# Poloneira.net
KiCad netlist of a schematic drawn in EAGLE
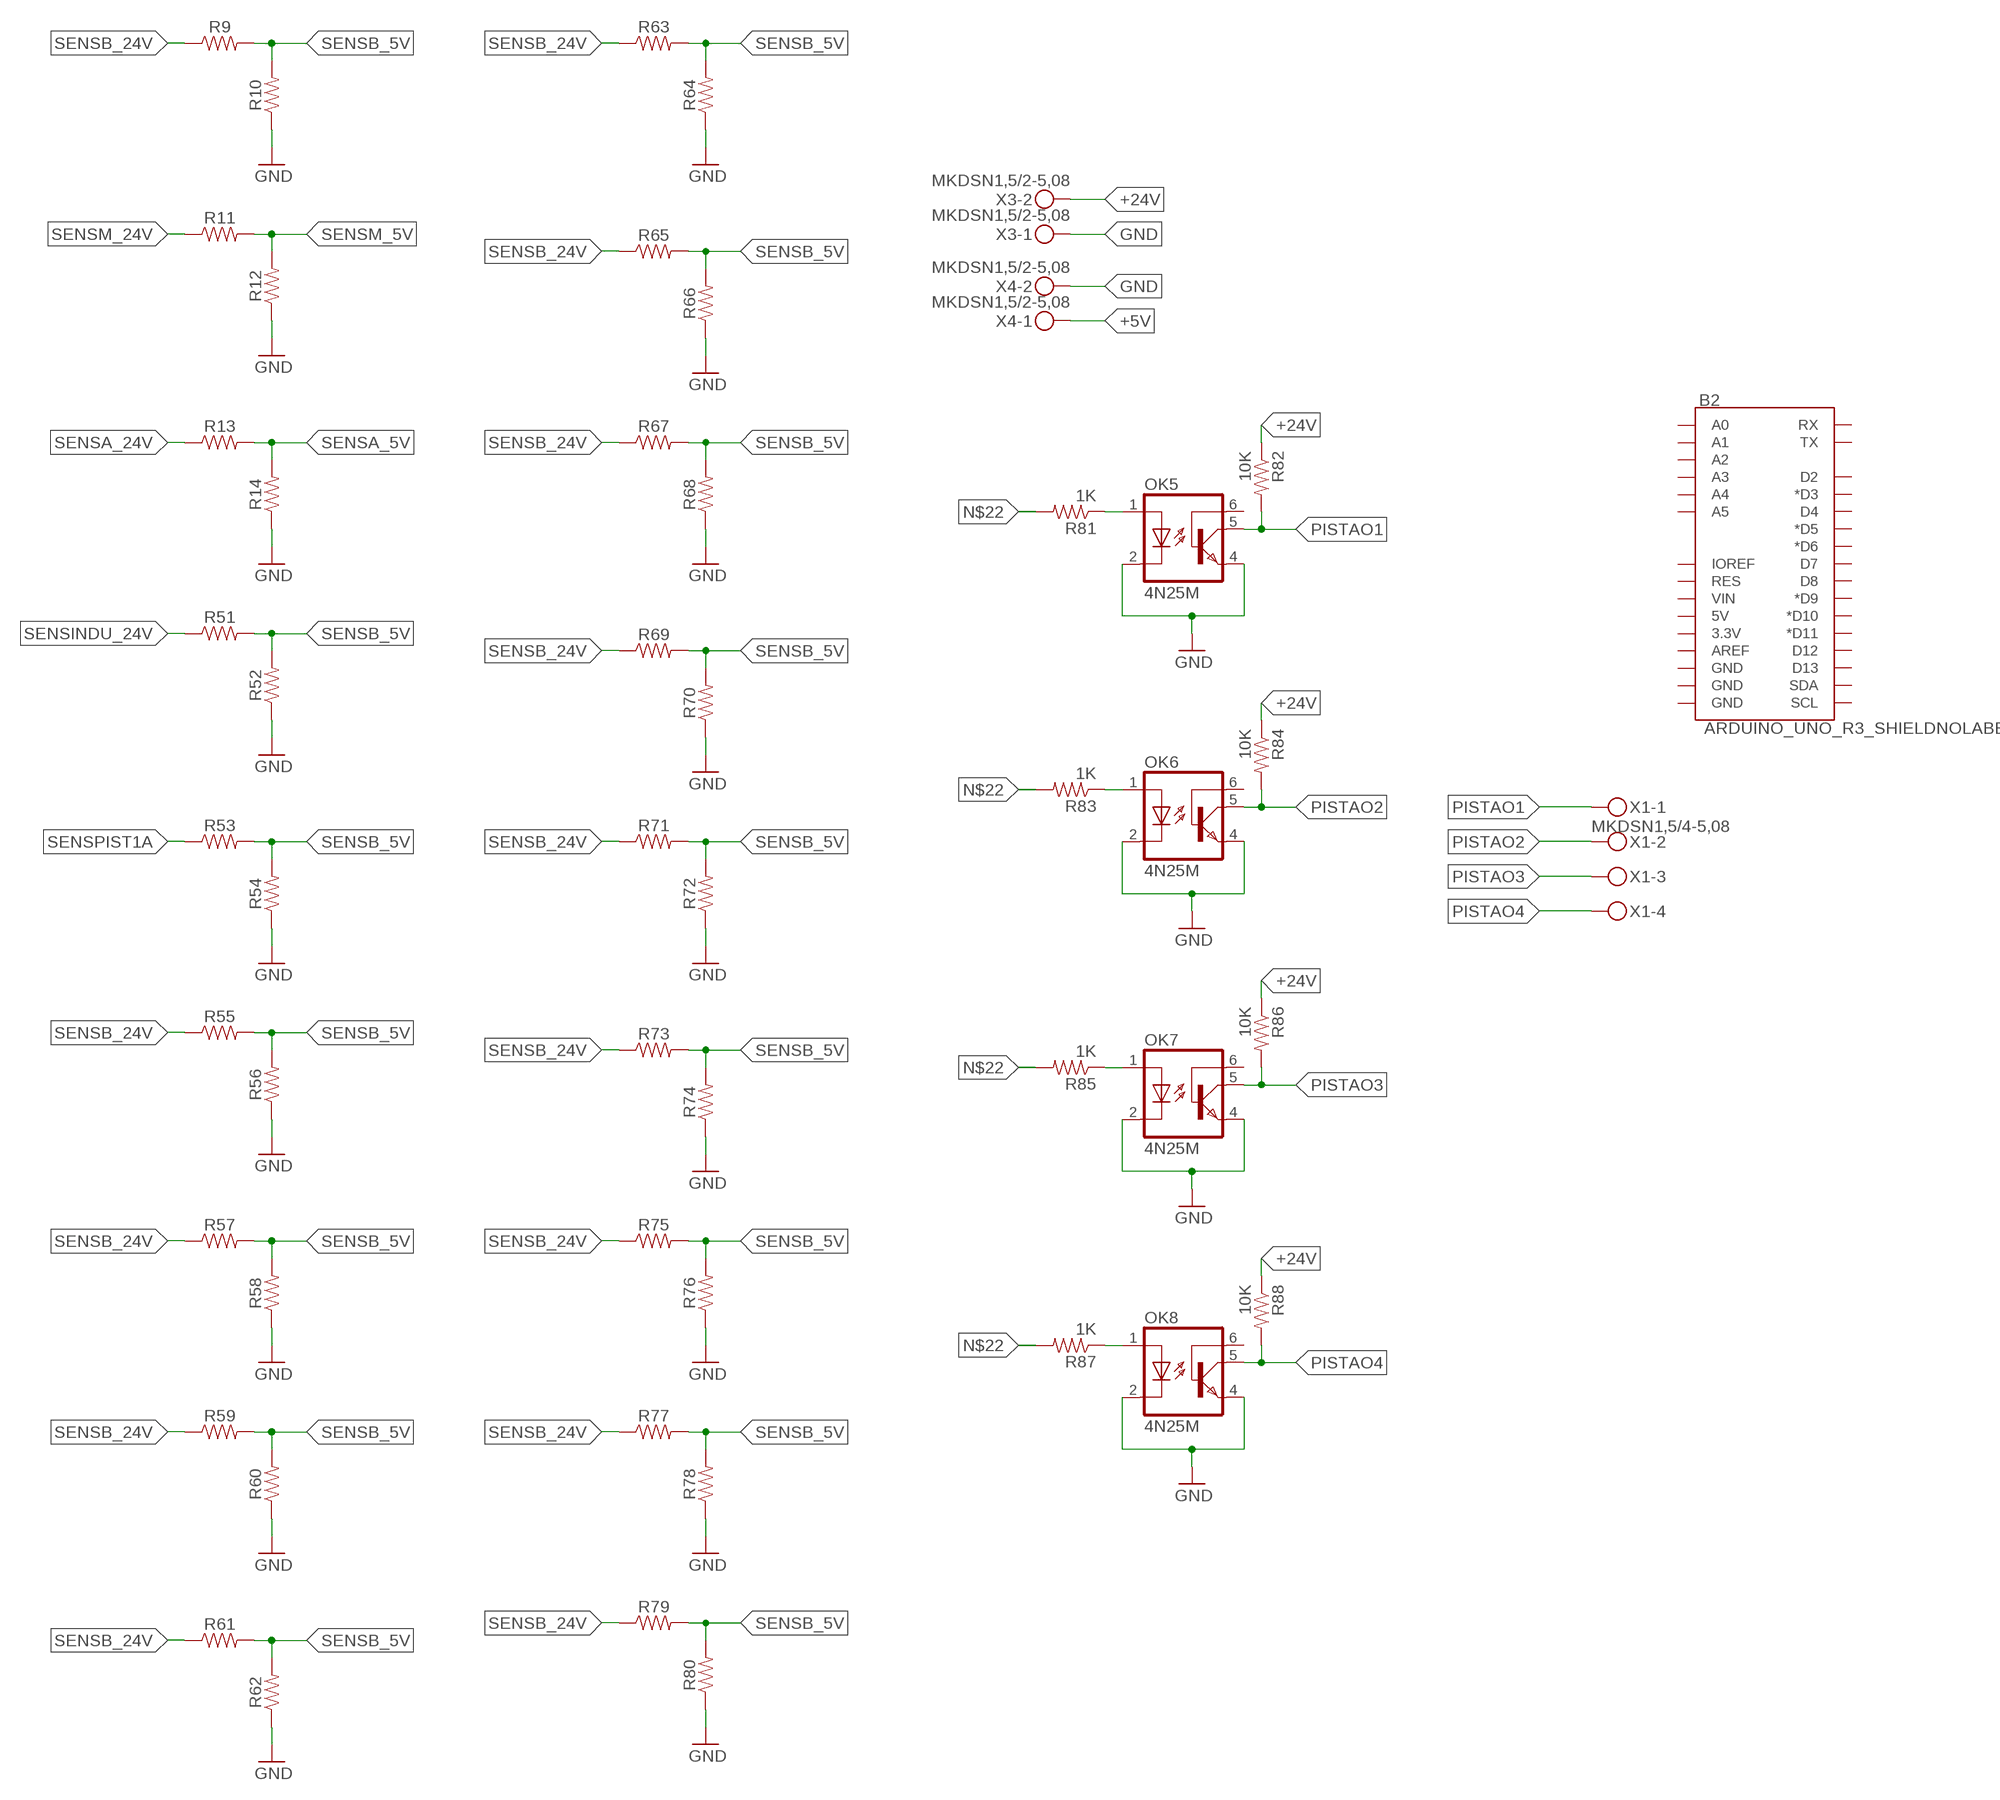
[diagram p0: schematic, sheet 1]

(export (version "E")
  (design (tool "Eeschema 10.0.6"))
  (components
    (comp (ref "B2")
      (value "ARDUINO_UNO_R3_SHIELDNOLABELS")
      (footprint "eagle-import:UNO_R3_SHIELD_NOLABELS")
      (libsource (lib "eagle-import") (part "ARDUINO_UNO_R3_SHIELDNOLABELS"))
    )
    (comp (ref "OK5")
      (value "4N25M")
      (footprint "eagle-import:DIL06")
      (fields (field (name "MPN") "4N25-M"))
      (libsource (lib "eagle-import") (part "4N?M25"))
    )
    (comp (ref "OK6")
      (value "4N25M")
      (footprint "eagle-import:DIL06")
      (fields (field (name "MPN") "4N25-M"))
      (libsource (lib "eagle-import") (part "4N?M25"))
    )
    (comp (ref "OK7")
      (value "4N25M")
      (footprint "eagle-import:DIL06")
      (fields (field (name "MPN") "4N25-M"))
      (libsource (lib "eagle-import") (part "4N?M25"))
    )
    (comp (ref "OK8")
      (value "4N25M")
      (footprint "eagle-import:DIL06")
      (fields (field (name "MPN") "4N25-M"))
      (libsource (lib "eagle-import") (part "4N?M25"))
    )
    (comp (ref "R9")
      (value "RESISTORAXIAL-0.3-KIT")
      (footprint "eagle-import:AXIAL-0.3-KIT")
      (libsource (lib "eagle-import") (part "RESISTORAXIAL-0.3-KIT"))
    )
    (comp (ref "R10")
      (value "RESISTORAXIAL-0.3-KIT")
      (footprint "eagle-import:AXIAL-0.3-KIT")
      (libsource (lib "eagle-import") (part "RESISTORAXIAL-0.3-KIT"))
    )
    (comp (ref "R11")
      (value "RESISTORAXIAL-0.3-KIT")
      (footprint "eagle-import:AXIAL-0.3-KIT")
      (libsource (lib "eagle-import") (part "RESISTORAXIAL-0.3-KIT"))
    )
    (comp (ref "R12")
      (value "RESISTORAXIAL-0.3-KIT")
      (footprint "eagle-import:AXIAL-0.3-KIT")
      (libsource (lib "eagle-import") (part "RESISTORAXIAL-0.3-KIT"))
    )
    (comp (ref "R13")
      (value "RESISTORAXIAL-0.3-KIT")
      (footprint "eagle-import:AXIAL-0.3-KIT")
      (libsource (lib "eagle-import") (part "RESISTORAXIAL-0.3-KIT"))
    )
    (comp (ref "R14")
      (value "RESISTORAXIAL-0.3-KIT")
      (footprint "eagle-import:AXIAL-0.3-KIT")
      (libsource (lib "eagle-import") (part "RESISTORAXIAL-0.3-KIT"))
    )
    (comp (ref "R51")
      (value "RESISTORAXIAL-0.3-KIT")
      (footprint "eagle-import:AXIAL-0.3-KIT")
      (libsource (lib "eagle-import") (part "RESISTORAXIAL-0.3-KIT"))
    )
    (comp (ref "R52")
      (value "RESISTORAXIAL-0.3-KIT")
      (footprint "eagle-import:AXIAL-0.3-KIT")
      (libsource (lib "eagle-import") (part "RESISTORAXIAL-0.3-KIT"))
    )
    (comp (ref "R53")
      (value "RESISTORAXIAL-0.3-KIT")
      (footprint "eagle-import:AXIAL-0.3-KIT")
      (libsource (lib "eagle-import") (part "RESISTORAXIAL-0.3-KIT"))
    )
    (comp (ref "R54")
      (value "RESISTORAXIAL-0.3-KIT")
      (footprint "eagle-import:AXIAL-0.3-KIT")
      (libsource (lib "eagle-import") (part "RESISTORAXIAL-0.3-KIT"))
    )
    (comp (ref "R55")
      (value "RESISTORAXIAL-0.3-KIT")
      (footprint "eagle-import:AXIAL-0.3-KIT")
      (libsource (lib "eagle-import") (part "RESISTORAXIAL-0.3-KIT"))
    )
    (comp (ref "R56")
      (value "RESISTORAXIAL-0.3-KIT")
      (footprint "eagle-import:AXIAL-0.3-KIT")
      (libsource (lib "eagle-import") (part "RESISTORAXIAL-0.3-KIT"))
    )
    (comp (ref "R57")
      (value "RESISTORAXIAL-0.3-KIT")
      (footprint "eagle-import:AXIAL-0.3-KIT")
      (libsource (lib "eagle-import") (part "RESISTORAXIAL-0.3-KIT"))
    )
    (comp (ref "R58")
      (value "RESISTORAXIAL-0.3-KIT")
      (footprint "eagle-import:AXIAL-0.3-KIT")
      (libsource (lib "eagle-import") (part "RESISTORAXIAL-0.3-KIT"))
    )
    (comp (ref "R59")
      (value "RESISTORAXIAL-0.3-KIT")
      (footprint "eagle-import:AXIAL-0.3-KIT")
      (libsource (lib "eagle-import") (part "RESISTORAXIAL-0.3-KIT"))
    )
    (comp (ref "R60")
      (value "RESISTORAXIAL-0.3-KIT")
      (footprint "eagle-import:AXIAL-0.3-KIT")
      (libsource (lib "eagle-import") (part "RESISTORAXIAL-0.3-KIT"))
    )
    (comp (ref "R61")
      (value "RESISTORAXIAL-0.3-KIT")
      (footprint "eagle-import:AXIAL-0.3-KIT")
      (libsource (lib "eagle-import") (part "RESISTORAXIAL-0.3-KIT"))
    )
    (comp (ref "R62")
      (value "RESISTORAXIAL-0.3-KIT")
      (footprint "eagle-import:AXIAL-0.3-KIT")
      (libsource (lib "eagle-import") (part "RESISTORAXIAL-0.3-KIT"))
    )
    (comp (ref "R63")
      (value "RESISTORAXIAL-0.3-KIT")
      (footprint "eagle-import:AXIAL-0.3-KIT")
      (libsource (lib "eagle-import") (part "RESISTORAXIAL-0.3-KIT"))
    )
    (comp (ref "R64")
      (value "RESISTORAXIAL-0.3-KIT")
      (footprint "eagle-import:AXIAL-0.3-KIT")
      (libsource (lib "eagle-import") (part "RESISTORAXIAL-0.3-KIT"))
    )
    (comp (ref "R65")
      (value "RESISTORAXIAL-0.3-KIT")
      (footprint "eagle-import:AXIAL-0.3-KIT")
      (libsource (lib "eagle-import") (part "RESISTORAXIAL-0.3-KIT"))
    )
    (comp (ref "R66")
      (value "RESISTORAXIAL-0.3-KIT")
      (footprint "eagle-import:AXIAL-0.3-KIT")
      (libsource (lib "eagle-import") (part "RESISTORAXIAL-0.3-KIT"))
    )
    (comp (ref "R67")
      (value "RESISTORAXIAL-0.3-KIT")
      (footprint "eagle-import:AXIAL-0.3-KIT")
      (libsource (lib "eagle-import") (part "RESISTORAXIAL-0.3-KIT"))
    )
    (comp (ref "R68")
      (value "RESISTORAXIAL-0.3-KIT")
      (footprint "eagle-import:AXIAL-0.3-KIT")
      (libsource (lib "eagle-import") (part "RESISTORAXIAL-0.3-KIT"))
    )
    (comp (ref "R69")
      (value "RESISTORAXIAL-0.3-KIT")
      (footprint "eagle-import:AXIAL-0.3-KIT")
      (libsource (lib "eagle-import") (part "RESISTORAXIAL-0.3-KIT"))
    )
    (comp (ref "R70")
      (value "RESISTORAXIAL-0.3-KIT")
      (footprint "eagle-import:AXIAL-0.3-KIT")
      (libsource (lib "eagle-import") (part "RESISTORAXIAL-0.3-KIT"))
    )
    (comp (ref "R71")
      (value "RESISTORAXIAL-0.3-KIT")
      (footprint "eagle-import:AXIAL-0.3-KIT")
      (libsource (lib "eagle-import") (part "RESISTORAXIAL-0.3-KIT"))
    )
    (comp (ref "R72")
      (value "RESISTORAXIAL-0.3-KIT")
      (footprint "eagle-import:AXIAL-0.3-KIT")
      (libsource (lib "eagle-import") (part "RESISTORAXIAL-0.3-KIT"))
    )
    (comp (ref "R73")
      (value "RESISTORAXIAL-0.3-KIT")
      (footprint "eagle-import:AXIAL-0.3-KIT")
      (libsource (lib "eagle-import") (part "RESISTORAXIAL-0.3-KIT"))
    )
    (comp (ref "R74")
      (value "RESISTORAXIAL-0.3-KIT")
      (footprint "eagle-import:AXIAL-0.3-KIT")
      (libsource (lib "eagle-import") (part "RESISTORAXIAL-0.3-KIT"))
    )
    (comp (ref "R75")
      (value "RESISTORAXIAL-0.3-KIT")
      (footprint "eagle-import:AXIAL-0.3-KIT")
      (libsource (lib "eagle-import") (part "RESISTORAXIAL-0.3-KIT"))
    )
    (comp (ref "R76")
      (value "RESISTORAXIAL-0.3-KIT")
      (footprint "eagle-import:AXIAL-0.3-KIT")
      (libsource (lib "eagle-import") (part "RESISTORAXIAL-0.3-KIT"))
    )
    (comp (ref "R77")
      (value "RESISTORAXIAL-0.3-KIT")
      (footprint "eagle-import:AXIAL-0.3-KIT")
      (libsource (lib "eagle-import") (part "RESISTORAXIAL-0.3-KIT"))
    )
    (comp (ref "R78")
      (value "RESISTORAXIAL-0.3-KIT")
      (footprint "eagle-import:AXIAL-0.3-KIT")
      (libsource (lib "eagle-import") (part "RESISTORAXIAL-0.3-KIT"))
    )
    (comp (ref "R79")
      (value "RESISTORAXIAL-0.3-KIT")
      (footprint "eagle-import:AXIAL-0.3-KIT")
      (libsource (lib "eagle-import") (part "RESISTORAXIAL-0.3-KIT"))
    )
    (comp (ref "R80")
      (value "RESISTORAXIAL-0.3-KIT")
      (footprint "eagle-import:AXIAL-0.3-KIT")
      (libsource (lib "eagle-import") (part "RESISTORAXIAL-0.3-KIT"))
    )
    (comp (ref "R81")
      (value "1K")
      (footprint "eagle-import:AXIAL-0.3EZ")
      (libsource (lib "eagle-import") (part "1KOHM-1/4W-1%(PTH)HORIZ-KIT"))
    )
    (comp (ref "R82")
      (value "10K")
      (footprint "eagle-import:AXIAL-0.3EZ")
      (libsource (lib "eagle-import") (part "1KOHM-1/4W-1%(PTH)HORIZ-KIT"))
    )
    (comp (ref "R83")
      (value "1K")
      (footprint "eagle-import:AXIAL-0.3EZ")
      (libsource (lib "eagle-import") (part "1KOHM-1/4W-1%(PTH)HORIZ-KIT"))
    )
    (comp (ref "R84")
      (value "10K")
      (footprint "eagle-import:AXIAL-0.3EZ")
      (libsource (lib "eagle-import") (part "1KOHM-1/4W-1%(PTH)HORIZ-KIT"))
    )
    (comp (ref "R85")
      (value "1K")
      (footprint "eagle-import:AXIAL-0.3EZ")
      (libsource (lib "eagle-import") (part "1KOHM-1/4W-1%(PTH)HORIZ-KIT"))
    )
    (comp (ref "R86")
      (value "10K")
      (footprint "eagle-import:AXIAL-0.3EZ")
      (libsource (lib "eagle-import") (part "1KOHM-1/4W-1%(PTH)HORIZ-KIT"))
    )
    (comp (ref "R87")
      (value "1K")
      (footprint "eagle-import:AXIAL-0.3EZ")
      (libsource (lib "eagle-import") (part "1KOHM-1/4W-1%(PTH)HORIZ-KIT"))
    )
    (comp (ref "R88")
      (value "10K")
      (footprint "eagle-import:AXIAL-0.3EZ")
      (libsource (lib "eagle-import") (part "1KOHM-1/4W-1%(PTH)HORIZ-KIT"))
    )
    (comp (ref "X1")
      (value "MKDSN1,5/4-5,08")
      (footprint "eagle-import:MKDSN1,5_4-5,08")
      (libsource (lib "eagle-import") (part "MKDSN1,5/4-5,08"))
    )
    (comp (ref "X3")
      (value "MKDSN1,5/2-5,08")
      (footprint "eagle-import:MKDSN1,5_2-5,08")
      (libsource (lib "eagle-import") (part "MKDSN1,5/2-5,08"))
    )
    (comp (ref "X4")
      (value "MKDSN1,5/2-5,08")
      (footprint "eagle-import:MKDSN1,5_2-5,08")
      (libsource (lib "eagle-import") (part "MKDSN1,5/2-5,08"))
    )
  )
  (nets
    (net (code "1") (name "+5V") (class "Default")
      (node (ref "X4") (pin "1") (pinfunction "KL_1") (pintype "passive"))
    )
    (net (code "2") (name "+24V") (class "Default")
      (node (ref "R82") (pin "P$1") (pinfunction "1_P$1") (pintype "passive"))
      (node (ref "R84") (pin "P$1") (pinfunction "1_P$1") (pintype "passive"))
      (node (ref "R86") (pin "P$1") (pinfunction "1_P$1") (pintype "passive"))
      (node (ref "R88") (pin "P$1") (pinfunction "1_P$1") (pintype "passive"))
      (node (ref "X3") (pin "2") (pinfunction "KL_2") (pintype "passive"))
    )
    (net (code "3") (name "GND") (class "Default")
      (node (ref "OK5") (pin "2") (pinfunction "C_2") (pintype "passive"))
      (node (ref "OK5") (pin "4") (pinfunction "EMI_4") (pintype "passive"))
      (node (ref "OK6") (pin "2") (pinfunction "C_2") (pintype "passive"))
      (node (ref "OK6") (pin "4") (pinfunction "EMI_4") (pintype "passive"))
      (node (ref "OK7") (pin "2") (pinfunction "C_2") (pintype "passive"))
      (node (ref "OK7") (pin "4") (pinfunction "EMI_4") (pintype "passive"))
      (node (ref "OK8") (pin "2") (pinfunction "C_2") (pintype "passive"))
      (node (ref "OK8") (pin "4") (pinfunction "EMI_4") (pintype "passive"))
      (node (ref "R10") (pin "P$1") (pinfunction "1_P$1") (pintype "passive"))
      (node (ref "R12") (pin "P$1") (pinfunction "1_P$1") (pintype "passive"))
      (node (ref "R14") (pin "P$1") (pinfunction "1_P$1") (pintype "passive"))
      (node (ref "R52") (pin "P$1") (pinfunction "1_P$1") (pintype "passive"))
      (node (ref "R54") (pin "P$1") (pinfunction "1_P$1") (pintype "passive"))
      (node (ref "R56") (pin "P$1") (pinfunction "1_P$1") (pintype "passive"))
      (node (ref "R58") (pin "P$1") (pinfunction "1_P$1") (pintype "passive"))
      (node (ref "R60") (pin "P$1") (pinfunction "1_P$1") (pintype "passive"))
      (node (ref "R62") (pin "P$1") (pinfunction "1_P$1") (pintype "passive"))
      (node (ref "R64") (pin "P$1") (pinfunction "1_P$1") (pintype "passive"))
      (node (ref "R66") (pin "P$1") (pinfunction "1_P$1") (pintype "passive"))
      (node (ref "R68") (pin "P$1") (pinfunction "1_P$1") (pintype "passive"))
      (node (ref "R70") (pin "P$1") (pinfunction "1_P$1") (pintype "passive"))
      (node (ref "R72") (pin "P$1") (pinfunction "1_P$1") (pintype "passive"))
      (node (ref "R74") (pin "P$1") (pinfunction "1_P$1") (pintype "passive"))
      (node (ref "R76") (pin "P$1") (pinfunction "1_P$1") (pintype "passive"))
      (node (ref "R78") (pin "P$1") (pinfunction "1_P$1") (pintype "passive"))
      (node (ref "R80") (pin "P$1") (pinfunction "1_P$1") (pintype "passive"))
      (node (ref "X3") (pin "1") (pinfunction "KL_1") (pintype "passive"))
      (node (ref "X4") (pin "2") (pinfunction "KL_2") (pintype "passive"))
    )
    (net (code "4") (name "N$22") (class "Default")
      (node (ref "R81") (pin "P$2") (pinfunction "2_P$2") (pintype "passive"))
      (node (ref "R83") (pin "P$2") (pinfunction "2_P$2") (pintype "passive"))
      (node (ref "R85") (pin "P$2") (pinfunction "2_P$2") (pintype "passive"))
      (node (ref "R87") (pin "P$2") (pinfunction "2_P$2") (pintype "passive"))
    )
    (net (code "5") (name "Net-(OK5-A)") (class "Default")
      (node (ref "OK5") (pin "1") (pinfunction "A_1") (pintype "passive"))
      (node (ref "R81") (pin "P$1") (pinfunction "1_P$1") (pintype "passive"))
    )
    (net (code "6") (name "Net-(OK6-A)") (class "Default")
      (node (ref "OK6") (pin "1") (pinfunction "A_1") (pintype "passive"))
      (node (ref "R83") (pin "P$1") (pinfunction "1_P$1") (pintype "passive"))
    )
    (net (code "7") (name "Net-(OK7-A)") (class "Default")
      (node (ref "OK7") (pin "1") (pinfunction "A_1") (pintype "passive"))
      (node (ref "R85") (pin "P$1") (pinfunction "1_P$1") (pintype "passive"))
    )
    (net (code "8") (name "Net-(OK8-A)") (class "Default")
      (node (ref "OK8") (pin "1") (pinfunction "A_1") (pintype "passive"))
      (node (ref "R87") (pin "P$1") (pinfunction "1_P$1") (pintype "passive"))
    )
    (net (code "9") (name "PISTAO1") (class "Default")
      (node (ref "OK5") (pin "5") (pinfunction "COL_5") (pintype "passive"))
      (node (ref "R82") (pin "P$2") (pinfunction "2_P$2") (pintype "passive"))
      (node (ref "X1") (pin "1") (pinfunction "KL_1") (pintype "passive"))
    )
    (net (code "10") (name "PISTAO2") (class "Default")
      (node (ref "OK6") (pin "5") (pinfunction "COL_5") (pintype "passive"))
      (node (ref "R84") (pin "P$2") (pinfunction "2_P$2") (pintype "passive"))
      (node (ref "X1") (pin "2") (pinfunction "KL_2") (pintype "passive"))
    )
    (net (code "11") (name "PISTAO3") (class "Default")
      (node (ref "OK7") (pin "5") (pinfunction "COL_5") (pintype "passive"))
      (node (ref "R86") (pin "P$2") (pinfunction "2_P$2") (pintype "passive"))
      (node (ref "X1") (pin "3") (pinfunction "KL_3") (pintype "passive"))
    )
    (net (code "12") (name "PISTAO4") (class "Default")
      (node (ref "OK8") (pin "5") (pinfunction "COL_5") (pintype "passive"))
      (node (ref "R88") (pin "P$2") (pinfunction "2_P$2") (pintype "passive"))
      (node (ref "X1") (pin "4") (pinfunction "KL_4") (pintype "passive"))
    )
    (net (code "13") (name "SENSA_5V") (class "Default")
      (node (ref "R13") (pin "P$2") (pinfunction "2_P$2") (pintype "passive"))
      (node (ref "R14") (pin "P$2") (pinfunction "2_P$2") (pintype "passive"))
    )
    (net (code "14") (name "SENSA_24V") (class "Default")
      (node (ref "R13") (pin "P$1") (pinfunction "1_P$1") (pintype "passive"))
    )
    (net (code "15") (name "SENSB_5V") (class "Default")
      (node (ref "R10") (pin "P$2") (pinfunction "2_P$2") (pintype "passive"))
      (node (ref "R51") (pin "P$2") (pinfunction "2_P$2") (pintype "passive"))
      (node (ref "R52") (pin "P$2") (pinfunction "2_P$2") (pintype "passive"))
      (node (ref "R53") (pin "P$2") (pinfunction "2_P$2") (pintype "passive"))
      (node (ref "R54") (pin "P$2") (pinfunction "2_P$2") (pintype "passive"))
      (node (ref "R55") (pin "P$2") (pinfunction "2_P$2") (pintype "passive"))
      (node (ref "R56") (pin "P$2") (pinfunction "2_P$2") (pintype "passive"))
      (node (ref "R57") (pin "P$2") (pinfunction "2_P$2") (pintype "passive"))
      (node (ref "R58") (pin "P$2") (pinfunction "2_P$2") (pintype "passive"))
      (node (ref "R59") (pin "P$2") (pinfunction "2_P$2") (pintype "passive"))
      (node (ref "R60") (pin "P$2") (pinfunction "2_P$2") (pintype "passive"))
      (node (ref "R61") (pin "P$2") (pinfunction "2_P$2") (pintype "passive"))
      (node (ref "R62") (pin "P$2") (pinfunction "2_P$2") (pintype "passive"))
      (node (ref "R63") (pin "P$2") (pinfunction "2_P$2") (pintype "passive"))
      (node (ref "R64") (pin "P$2") (pinfunction "2_P$2") (pintype "passive"))
      (node (ref "R65") (pin "P$2") (pinfunction "2_P$2") (pintype "passive"))
      (node (ref "R66") (pin "P$2") (pinfunction "2_P$2") (pintype "passive"))
      (node (ref "R67") (pin "P$2") (pinfunction "2_P$2") (pintype "passive"))
      (node (ref "R68") (pin "P$2") (pinfunction "2_P$2") (pintype "passive"))
      (node (ref "R69") (pin "P$2") (pinfunction "2_P$2") (pintype "passive"))
      (node (ref "R70") (pin "P$2") (pinfunction "2_P$2") (pintype "passive"))
      (node (ref "R71") (pin "P$2") (pinfunction "2_P$2") (pintype "passive"))
      (node (ref "R72") (pin "P$2") (pinfunction "2_P$2") (pintype "passive"))
      (node (ref "R73") (pin "P$2") (pinfunction "2_P$2") (pintype "passive"))
      (node (ref "R74") (pin "P$2") (pinfunction "2_P$2") (pintype "passive"))
      (node (ref "R75") (pin "P$2") (pinfunction "2_P$2") (pintype "passive"))
      (node (ref "R76") (pin "P$2") (pinfunction "2_P$2") (pintype "passive"))
      (node (ref "R77") (pin "P$2") (pinfunction "2_P$2") (pintype "passive"))
      (node (ref "R78") (pin "P$2") (pinfunction "2_P$2") (pintype "passive"))
      (node (ref "R79") (pin "P$2") (pinfunction "2_P$2") (pintype "passive"))
      (node (ref "R80") (pin "P$2") (pinfunction "2_P$2") (pintype "passive"))
      (node (ref "R9") (pin "P$2") (pinfunction "2_P$2") (pintype "passive"))
    )
    (net (code "16") (name "SENSB_24V") (class "Default")
      (node (ref "R55") (pin "P$1") (pinfunction "1_P$1") (pintype "passive"))
      (node (ref "R57") (pin "P$1") (pinfunction "1_P$1") (pintype "passive"))
      (node (ref "R59") (pin "P$1") (pinfunction "1_P$1") (pintype "passive"))
      (node (ref "R61") (pin "P$1") (pinfunction "1_P$1") (pintype "passive"))
      (node (ref "R63") (pin "P$1") (pinfunction "1_P$1") (pintype "passive"))
      (node (ref "R65") (pin "P$1") (pinfunction "1_P$1") (pintype "passive"))
      (node (ref "R67") (pin "P$1") (pinfunction "1_P$1") (pintype "passive"))
      (node (ref "R69") (pin "P$1") (pinfunction "1_P$1") (pintype "passive"))
      (node (ref "R71") (pin "P$1") (pinfunction "1_P$1") (pintype "passive"))
      (node (ref "R73") (pin "P$1") (pinfunction "1_P$1") (pintype "passive"))
      (node (ref "R75") (pin "P$1") (pinfunction "1_P$1") (pintype "passive"))
      (node (ref "R77") (pin "P$1") (pinfunction "1_P$1") (pintype "passive"))
      (node (ref "R79") (pin "P$1") (pinfunction "1_P$1") (pintype "passive"))
      (node (ref "R9") (pin "P$1") (pinfunction "1_P$1") (pintype "passive"))
    )
    (net (code "17") (name "SENSINDU_24V") (class "Default")
      (node (ref "R51") (pin "P$1") (pinfunction "1_P$1") (pintype "passive"))
    )
    (net (code "18") (name "SENSM_5V") (class "Default")
      (node (ref "R11") (pin "P$2") (pinfunction "2_P$2") (pintype "passive"))
      (node (ref "R12") (pin "P$2") (pinfunction "2_P$2") (pintype "passive"))
    )
    (net (code "19") (name "SENSM_24V") (class "Default")
      (node (ref "R11") (pin "P$1") (pinfunction "1_P$1") (pintype "passive"))
    )
    (net (code "20") (name "SENSPIST1A") (class "Default")
      (node (ref "R53") (pin "P$1") (pinfunction "1_P$1") (pintype "passive"))
    )
    (net (code "21") (name "unconnected-(B2-*D3-PadD3)") (class "Default")
      (node (ref "B2") (pin "D3") (pinfunction "*D3_D3") (pintype "bidirectional"))
    )
    (net (code "22") (name "unconnected-(B2-*D5-PadD5)") (class "Default")
      (node (ref "B2") (pin "D5") (pinfunction "*D5_D5") (pintype "bidirectional"))
    )
    (net (code "23") (name "unconnected-(B2-*D6-PadD6)") (class "Default")
      (node (ref "B2") (pin "D6") (pinfunction "*D6_D6") (pintype "bidirectional"))
    )
    (net (code "24") (name "unconnected-(B2-*D9-PadD9)") (class "Default")
      (node (ref "B2") (pin "D9") (pinfunction "*D9_D9") (pintype "bidirectional"))
    )
    (net (code "25") (name "unconnected-(B2-*D10-PadD10)") (class "Default")
      (node (ref "B2") (pin "D10") (pinfunction "*D10_D10") (pintype "bidirectional"))
    )
    (net (code "26") (name "unconnected-(B2-*D11-PadD11)") (class "Default")
      (node (ref "B2") (pin "D11") (pinfunction "*D11_D11") (pintype "bidirectional"))
    )
    (net (code "27") (name "unconnected-(B2-GND-PadGND@0)") (class "Default")
      (node (ref "B2") (pin "GND@0") (pinfunction "GND_GND@0") (pintype "bidirectional"))
    )
    (net (code "28") (name "unconnected-(B2-GND-PadGND@1)") (class "Default")
      (node (ref "B2") (pin "GND@1") (pinfunction "GND_GND@1") (pintype "bidirectional"))
    )
    (net (code "29") (name "unconnected-(B2-GND-PadGND@2)") (class "Default")
      (node (ref "B2") (pin "GND@2") (pinfunction "GND_GND@2") (pintype "bidirectional"))
    )
    (net (code "30") (name "unconnected-(B2-Pad3.3V)") (class "Default")
      (node (ref "B2") (pin "3.3V") (pinfunction "3.3V_3.3V") (pintype "bidirectional"))
    )
    (net (code "31") (name "unconnected-(B2-Pad5V)") (class "Default")
      (node (ref "B2") (pin "5V") (pinfunction "5V_5V") (pintype "bidirectional"))
    )
    (net (code "32") (name "unconnected-(B2-PadA0)") (class "Default")
      (node (ref "B2") (pin "A0") (pinfunction "A0_A0") (pintype "bidirectional"))
    )
    (net (code "33") (name "unconnected-(B2-PadA1)") (class "Default")
      (node (ref "B2") (pin "A1") (pinfunction "A1_A1") (pintype "bidirectional"))
    )
    (net (code "34") (name "unconnected-(B2-PadA2)") (class "Default")
      (node (ref "B2") (pin "A2") (pinfunction "A2_A2") (pintype "bidirectional"))
    )
    (net (code "35") (name "unconnected-(B2-PadA3)") (class "Default")
      (node (ref "B2") (pin "A3") (pinfunction "A3_A3") (pintype "bidirectional"))
    )
    (net (code "36") (name "unconnected-(B2-PadA4)") (class "Default")
      (node (ref "B2") (pin "A4") (pinfunction "A4_A4") (pintype "bidirectional"))
    )
    (net (code "37") (name "unconnected-(B2-PadA5)") (class "Default")
      (node (ref "B2") (pin "A5") (pinfunction "A5_A5") (pintype "bidirectional"))
    )
    (net (code "38") (name "unconnected-(B2-PadAREF)") (class "Default")
      (node (ref "B2") (pin "AREF") (pinfunction "AREF_AREF") (pintype "bidirectional"))
    )
    (net (code "39") (name "unconnected-(B2-PadD2)") (class "Default")
      (node (ref "B2") (pin "D2") (pinfunction "D2_D2") (pintype "bidirectional"))
    )
    (net (code "40") (name "unconnected-(B2-PadD4)") (class "Default")
      (node (ref "B2") (pin "D4") (pinfunction "D4_D4") (pintype "bidirectional"))
    )
    (net (code "41") (name "unconnected-(B2-PadD7)") (class "Default")
      (node (ref "B2") (pin "D7") (pinfunction "D7_D7") (pintype "bidirectional"))
    )
    (net (code "42") (name "unconnected-(B2-PadD8)") (class "Default")
      (node (ref "B2") (pin "D8") (pinfunction "D8_D8") (pintype "bidirectional"))
    )
    (net (code "43") (name "unconnected-(B2-PadD12)") (class "Default")
      (node (ref "B2") (pin "D12") (pinfunction "D12_D12") (pintype "bidirectional"))
    )
    (net (code "44") (name "unconnected-(B2-PadD13)") (class "Default")
      (node (ref "B2") (pin "D13") (pinfunction "D13_D13") (pintype "bidirectional"))
    )
    (net (code "45") (name "unconnected-(B2-PadIOREF)") (class "Default")
      (node (ref "B2") (pin "IOREF") (pinfunction "IOREF_IOREF") (pintype "bidirectional"))
    )
    (net (code "46") (name "unconnected-(B2-PadRES)") (class "Default")
      (node (ref "B2") (pin "RES") (pinfunction "RES_RES") (pintype "bidirectional"))
    )
    (net (code "47") (name "unconnected-(B2-PadRX)") (class "Default")
      (node (ref "B2") (pin "RX") (pinfunction "RX_RX") (pintype "bidirectional"))
    )
    (net (code "48") (name "unconnected-(B2-PadSCL)") (class "Default")
      (node (ref "B2") (pin "SCL") (pinfunction "SCL_SCL") (pintype "bidirectional"))
    )
    (net (code "49") (name "unconnected-(B2-PadSDA)") (class "Default")
      (node (ref "B2") (pin "SDA") (pinfunction "SDA_SDA") (pintype "bidirectional"))
    )
    (net (code "50") (name "unconnected-(B2-PadTX)") (class "Default")
      (node (ref "B2") (pin "TX") (pinfunction "TX_TX") (pintype "bidirectional"))
    )
    (net (code "51") (name "unconnected-(B2-PadVIN)") (class "Default")
      (node (ref "B2") (pin "VIN") (pinfunction "VIN_VIN") (pintype "bidirectional"))
    )
    (net (code "52") (name "unconnected-(OK5-BAS-Pad6)") (class "Default")
      (node (ref "OK5") (pin "6") (pinfunction "BAS_6") (pintype "passive"))
    )
    (net (code "53") (name "unconnected-(OK6-BAS-Pad6)") (class "Default")
      (node (ref "OK6") (pin "6") (pinfunction "BAS_6") (pintype "passive"))
    )
    (net (code "54") (name "unconnected-(OK7-BAS-Pad6)") (class "Default")
      (node (ref "OK7") (pin "6") (pinfunction "BAS_6") (pintype "passive"))
    )
    (net (code "55") (name "unconnected-(OK8-BAS-Pad6)") (class "Default")
      (node (ref "OK8") (pin "6") (pinfunction "BAS_6") (pintype "passive"))
    )
  )
)
